# XStepper.net
KiCad netlist of a schematic drawn in EAGLE
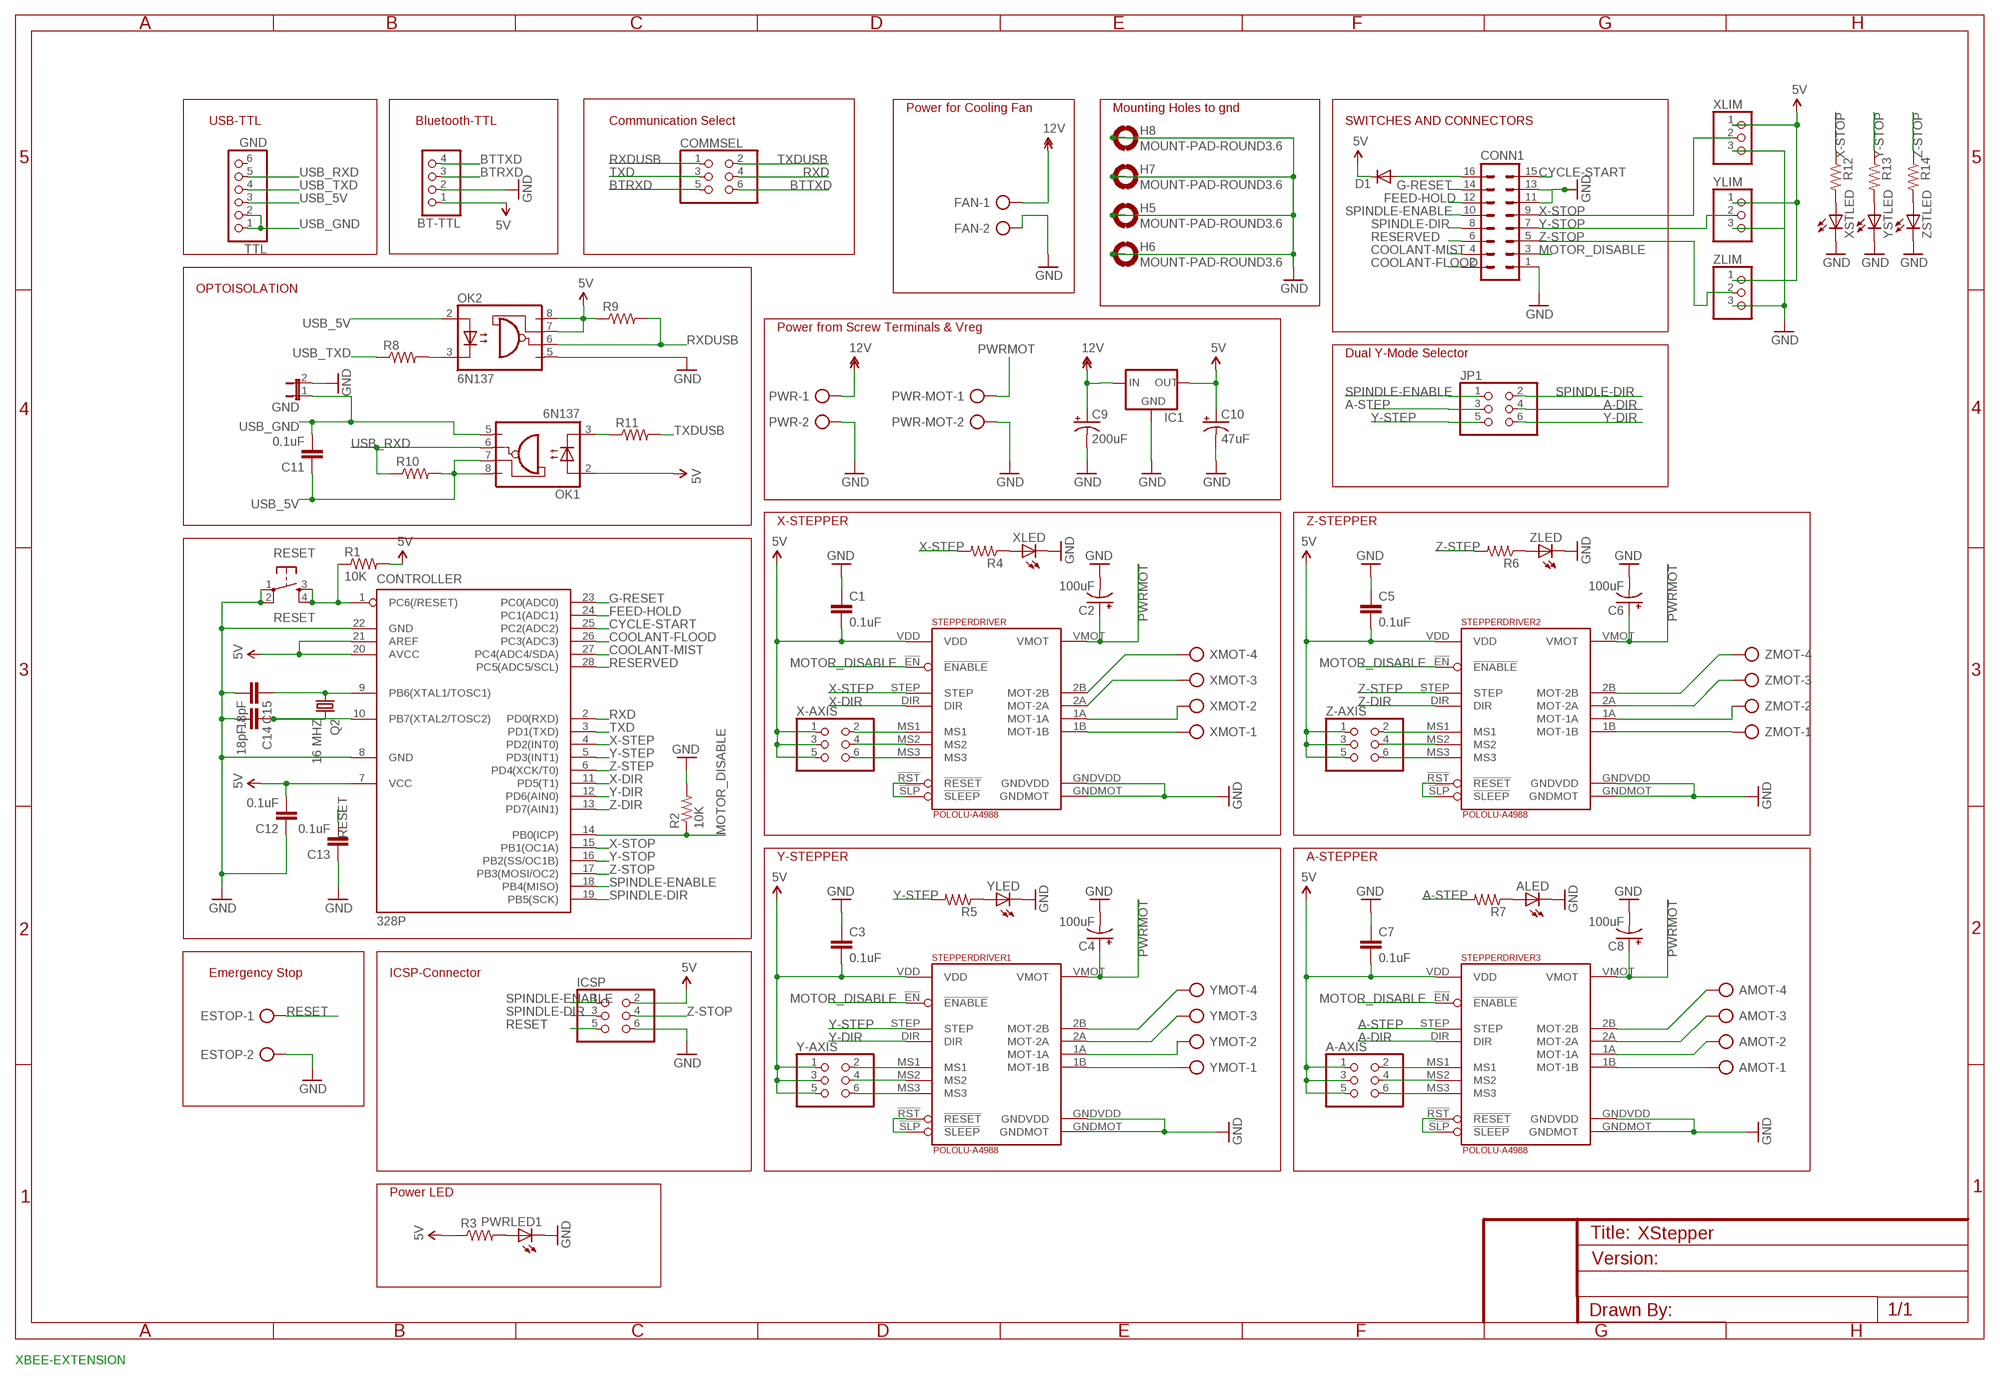
[diagram p0: schematic, sheet 1]

(export (version "E")
  (design (tool "Eeschema 10.0.6"))
  (components
    (comp (ref "328P")
      (value "CONTROLLER")
      (footprint "eagle-import:DIL28-3")
      (libsource (lib "eagle-import") (part "MEGA8-P"))
    )
    (comp (ref "A-AXIS")
      (value "PINHD-2X3")
      (footprint "eagle-import:2X03")
      (libsource (lib "eagle-import") (part "PINHD-2X3"))
    )
    (comp (ref "ALED")
      (value "LED3MM")
      (footprint "eagle-import:LED3MM")
      (libsource (lib "eagle-import") (part "LED3MM"))
    )
    (comp (ref "AMOT")
      (value "AK500/4")
      (footprint "eagle-import:AK500_4")
      (libsource (lib "eagle-import") (part "AK500/4"))
    )
    (comp (ref "BT-TTL")
      (value "PINHD-1X4")
      (footprint "eagle-import:1X04")
      (libsource (lib "eagle-import") (part "PINHD-1X4"))
    )
    (comp (ref "C1")
      (value "0.1uF")
      (footprint "eagle-import:C025-025X050")
      (libsource (lib "eagle-import") (part "C-EU025-025X050"))
    )
    (comp (ref "C2")
      (value "100uF")
      (footprint "eagle-import:E2,5-6")
      (libsource (lib "eagle-import") (part "CPOL-USE2.5-6"))
    )
    (comp (ref "C3")
      (value "0.1uF")
      (footprint "eagle-import:C025-025X050")
      (libsource (lib "eagle-import") (part "C-EU025-025X050"))
    )
    (comp (ref "C4")
      (value "100uF")
      (footprint "eagle-import:E2,5-6")
      (libsource (lib "eagle-import") (part "CPOL-USE2.5-6"))
    )
    (comp (ref "C5")
      (value "0.1uF")
      (footprint "eagle-import:C025-025X050")
      (libsource (lib "eagle-import") (part "C-EU025-025X050"))
    )
    (comp (ref "C6")
      (value "100uF")
      (footprint "eagle-import:E2,5-6")
      (libsource (lib "eagle-import") (part "CPOL-USE2.5-6"))
    )
    (comp (ref "C7")
      (value "0.1uF")
      (footprint "eagle-import:C025-025X050")
      (libsource (lib "eagle-import") (part "C-EU025-025X050"))
    )
    (comp (ref "C8")
      (value "100uF")
      (footprint "eagle-import:E2,5-6")
      (libsource (lib "eagle-import") (part "CPOL-USE2.5-6"))
    )
    (comp (ref "C9")
      (value "200uF")
      (footprint "eagle-import:E2,5-6")
      (libsource (lib "eagle-import") (part "CPOL-USE2.5-6"))
    )
    (comp (ref "C10")
      (value "47uF")
      (footprint "eagle-import:E2,5-6")
      (libsource (lib "eagle-import") (part "CPOL-USE2.5-6"))
    )
    (comp (ref "C11")
      (value "0.1uF")
      (footprint "eagle-import:C025-025X050")
      (libsource (lib "eagle-import") (part "C-EU025-025X050"))
    )
    (comp (ref "C12")
      (value "0.1uF")
      (footprint "eagle-import:C025-025X050")
      (libsource (lib "eagle-import") (part "C-EU025-025X050"))
    )
    (comp (ref "C13")
      (value "0.1uF")
      (footprint "eagle-import:C025-025X050")
      (libsource (lib "eagle-import") (part "C-EU025-025X050"))
    )
    (comp (ref "C14")
      (value "18pF")
      (footprint "eagle-import:C025-025X050")
      (libsource (lib "eagle-import") (part "C-EU025-025X050"))
    )
    (comp (ref "C15")
      (value "18pF")
      (footprint "eagle-import:C025-025X050")
      (libsource (lib "eagle-import") (part "C-EU025-025X050"))
    )
    (comp (ref "COMMSEL")
      (value "PINHD-2X3")
      (footprint "eagle-import:2X03")
      (libsource (lib "eagle-import") (part "PINHD-2X3"))
    )
    (comp (ref "CONN1")
      (value "ML16")
      (footprint "eagle-import:ML16")
      (libsource (lib "eagle-import") (part "ML16"))
    )
    (comp (ref "D1")
      (value "DIODEPTH")
      (footprint "eagle-import:DIODE-1N4001")
      (libsource (lib "eagle-import") (part "DIODEPTH"))
    )
    (comp (ref "ESTOP")
      (value "AK500/2")
      (footprint "eagle-import:AK500_2")
      (libsource (lib "eagle-import") (part "AK500/2"))
    )
    (comp (ref "FAN")
      (value "AK500/2")
      (footprint "eagle-import:AK500_2")
      (libsource (lib "eagle-import") (part "AK500/2"))
    )
    (comp (ref "GND")
      (value "JP1E")
      (footprint "eagle-import:JP1")
      (libsource (lib "eagle-import") (part "JP1E"))
    )
    (comp (ref "H5")
      (value "MOUNT-PAD-ROUND3.6")
      (footprint "eagle-import:3,6-PAD")
      (libsource (lib "eagle-import") (part "MOUNT-PAD-ROUND3.6"))
    )
    (comp (ref "H6")
      (value "MOUNT-PAD-ROUND3.6")
      (footprint "eagle-import:3,6-PAD")
      (libsource (lib "eagle-import") (part "MOUNT-PAD-ROUND3.6"))
    )
    (comp (ref "H7")
      (value "MOUNT-PAD-ROUND3.6")
      (footprint "eagle-import:3,6-PAD")
      (libsource (lib "eagle-import") (part "MOUNT-PAD-ROUND3.6"))
    )
    (comp (ref "H8")
      (value "MOUNT-PAD-ROUND3.6")
      (footprint "eagle-import:3,6-PAD")
      (libsource (lib "eagle-import") (part "MOUNT-PAD-ROUND3.6"))
    )
    (comp (ref "IC1")
      (value "V_REG_78XXSINK")
      (footprint "eagle-import:TO220-IGO")
      (libsource (lib "eagle-import") (part "V_REG_78XXSINK"))
    )
    (comp (ref "ICSP")
      (value "PINHD-2X3")
      (footprint "eagle-import:2X03")
      (libsource (lib "eagle-import") (part "PINHD-2X3"))
    )
    (comp (ref "JP1")
      (value "PINHD-2X3")
      (footprint "eagle-import:2X03")
      (libsource (lib "eagle-import") (part "PINHD-2X3"))
    )
    (comp (ref "OK1")
      (value "6N137")
      (footprint "eagle-import:DIL08")
      (libsource (lib "eagle-import") (part "6N137"))
    )
    (comp (ref "OK2")
      (value "6N137")
      (footprint "eagle-import:DIL08")
      (libsource (lib "eagle-import") (part "6N137"))
    )
    (comp (ref "PWR")
      (value "AK500/2")
      (footprint "eagle-import:AK500_2")
      (libsource (lib "eagle-import") (part "AK500/2"))
    )
    (comp (ref "PWR-MOT")
      (value "AK500/2")
      (footprint "eagle-import:AK500_2")
      (libsource (lib "eagle-import") (part "AK500/2"))
    )
    (comp (ref "PWRLED1")
      (value "LED3MM")
      (footprint "eagle-import:LED3MM")
      (libsource (lib "eagle-import") (part "LED3MM"))
    )
    (comp (ref "Q2")
      (value "16 MHZ")
      (footprint "eagle-import:HC49_S")
      (libsource (lib "eagle-import") (part "CRYSTALHC49S"))
    )
    (comp (ref "R1")
      (value "10K")
      (footprint "eagle-import:AXIAL-0.3")
      (libsource (lib "eagle-import") (part "RESISTORAXIAL-0.3"))
    )
    (comp (ref "R2")
      (value "10K")
      (footprint "eagle-import:AXIAL-0.3")
      (libsource (lib "eagle-import") (part "RESISTORAXIAL-0.3"))
    )
    (comp (ref "R3")
      (value "RESISTORAXIAL-0.3")
      (footprint "eagle-import:AXIAL-0.3")
      (libsource (lib "eagle-import") (part "RESISTORAXIAL-0.3"))
    )
    (comp (ref "R4")
      (value "RESISTORAXIAL-0.3")
      (footprint "eagle-import:AXIAL-0.3")
      (libsource (lib "eagle-import") (part "RESISTORAXIAL-0.3"))
    )
    (comp (ref "R5")
      (value "RESISTORAXIAL-0.3")
      (footprint "eagle-import:AXIAL-0.3")
      (libsource (lib "eagle-import") (part "RESISTORAXIAL-0.3"))
    )
    (comp (ref "R6")
      (value "RESISTORAXIAL-0.3")
      (footprint "eagle-import:AXIAL-0.3")
      (libsource (lib "eagle-import") (part "RESISTORAXIAL-0.3"))
    )
    (comp (ref "R7")
      (value "RESISTORAXIAL-0.3")
      (footprint "eagle-import:AXIAL-0.3")
      (libsource (lib "eagle-import") (part "RESISTORAXIAL-0.3"))
    )
    (comp (ref "R8")
      (value "RESISTORAXIAL-0.3")
      (footprint "eagle-import:AXIAL-0.3")
      (libsource (lib "eagle-import") (part "RESISTORAXIAL-0.3"))
    )
    (comp (ref "R9")
      (value "RESISTORAXIAL-0.3")
      (footprint "eagle-import:AXIAL-0.3")
      (libsource (lib "eagle-import") (part "RESISTORAXIAL-0.3"))
    )
    (comp (ref "R10")
      (value "RESISTORAXIAL-0.3")
      (footprint "eagle-import:AXIAL-0.3")
      (libsource (lib "eagle-import") (part "RESISTORAXIAL-0.3"))
    )
    (comp (ref "R11")
      (value "RESISTORAXIAL-0.3")
      (footprint "eagle-import:AXIAL-0.3")
      (libsource (lib "eagle-import") (part "RESISTORAXIAL-0.3"))
    )
    (comp (ref "R12")
      (value "RESISTORAXIAL-0.3")
      (footprint "eagle-import:AXIAL-0.3")
      (libsource (lib "eagle-import") (part "RESISTORAXIAL-0.3"))
    )
    (comp (ref "R13")
      (value "RESISTORAXIAL-0.3")
      (footprint "eagle-import:AXIAL-0.3")
      (libsource (lib "eagle-import") (part "RESISTORAXIAL-0.3"))
    )
    (comp (ref "R14")
      (value "RESISTORAXIAL-0.3")
      (footprint "eagle-import:AXIAL-0.3")
      (libsource (lib "eagle-import") (part "RESISTORAXIAL-0.3"))
    )
    (comp (ref "RESET")
      (value "RESET")
      (footprint "eagle-import:TACTILE-PTH")
      (libsource (lib "eagle-import") (part "TAC_SWITCHPTH"))
    )
    (comp (ref "STEPPERDRIVER")
      (value "POLOLU-A4988")
      (footprint "eagle-import:POLOLU-ALLEGRO-PTH")
      (libsource (lib "eagle-import") (part "POLOLU-ALLEGRO"))
    )
    (comp (ref "STEPPERDRIVER1")
      (value "POLOLU-A4988")
      (footprint "eagle-import:POLOLU-ALLEGRO-PTH")
      (libsource (lib "eagle-import") (part "POLOLU-ALLEGRO"))
    )
    (comp (ref "STEPPERDRIVER2")
      (value "POLOLU-A4988")
      (footprint "eagle-import:POLOLU-ALLEGRO-PTH")
      (libsource (lib "eagle-import") (part "POLOLU-ALLEGRO"))
    )
    (comp (ref "STEPPERDRIVER3")
      (value "POLOLU-A4988")
      (footprint "eagle-import:POLOLU-ALLEGRO-PTH")
      (libsource (lib "eagle-import") (part "POLOLU-ALLEGRO"))
    )
    (comp (ref "TTL")
      (value "GND")
      (footprint "eagle-import:1X06")
      (libsource (lib "eagle-import") (part "PINHD-1X6"))
    )
    (comp (ref "X-AXIS")
      (value "PINHD-2X3")
      (footprint "eagle-import:2X03")
      (libsource (lib "eagle-import") (part "PINHD-2X3"))
    )
    (comp (ref "XLED")
      (value "LED3MM")
      (footprint "eagle-import:LED3MM")
      (libsource (lib "eagle-import") (part "LED3MM"))
    )
    (comp (ref "XLIM")
      (value "PINHD-1X3")
      (footprint "eagle-import:1X03")
      (libsource (lib "eagle-import") (part "PINHD-1X3"))
    )
    (comp (ref "XMOT")
      (value "AK500/4")
      (footprint "eagle-import:AK500_4")
      (libsource (lib "eagle-import") (part "AK500/4"))
    )
    (comp (ref "XSTLED")
      (value "LED3MM")
      (footprint "eagle-import:LED3MM")
      (libsource (lib "eagle-import") (part "LED3MM"))
    )
    (comp (ref "Y-AXIS")
      (value "PINHD-2X3")
      (footprint "eagle-import:2X03")
      (libsource (lib "eagle-import") (part "PINHD-2X3"))
    )
    (comp (ref "YLED")
      (value "LED3MM")
      (footprint "eagle-import:LED3MM")
      (libsource (lib "eagle-import") (part "LED3MM"))
    )
    (comp (ref "YLIM")
      (value "PINHD-1X3")
      (footprint "eagle-import:1X03")
      (libsource (lib "eagle-import") (part "PINHD-1X3"))
    )
    (comp (ref "YMOT")
      (value "AK500/4")
      (footprint "eagle-import:AK500_4")
      (libsource (lib "eagle-import") (part "AK500/4"))
    )
    (comp (ref "YSTLED")
      (value "LED3MM")
      (footprint "eagle-import:LED3MM")
      (libsource (lib "eagle-import") (part "LED3MM"))
    )
    (comp (ref "Z-AXIS")
      (value "PINHD-2X3")
      (footprint "eagle-import:2X03")
      (libsource (lib "eagle-import") (part "PINHD-2X3"))
    )
    (comp (ref "ZLED")
      (value "LED3MM")
      (footprint "eagle-import:LED3MM")
      (libsource (lib "eagle-import") (part "LED3MM"))
    )
    (comp (ref "ZLIM")
      (value "PINHD-1X3")
      (footprint "eagle-import:1X03")
      (libsource (lib "eagle-import") (part "PINHD-1X3"))
    )
    (comp (ref "ZMOT")
      (value "AK500/4")
      (footprint "eagle-import:AK500_4")
      (libsource (lib "eagle-import") (part "AK500/4"))
    )
    (comp (ref "ZSTLED")
      (value "LED3MM")
      (footprint "eagle-import:LED3MM")
      (libsource (lib "eagle-import") (part "LED3MM"))
    )
  )
  (nets
    (net (code "1") (name "/A-DIR") (class "Default")
      (node (ref "JP1") (pin "4") (pinfunction "4_4") (pintype "passive"))
      (node (ref "STEPPERDRIVER3") (pin "DIR") (pinfunction "DIR_DIR") (pintype "bidirectional"))
    )
    (net (code "2") (name "/A-STEP") (class "Default")
      (node (ref "JP1") (pin "3") (pinfunction "3_3") (pintype "passive"))
      (node (ref "R7") (pin "P$2") (pinfunction "2_P$2") (pintype "passive"))
      (node (ref "STEPPERDRIVER3") (pin "STEP") (pinfunction "STEP_STEP") (pintype "bidirectional"))
    )
    (net (code "3") (name "/BTRXD") (class "Default")
      (node (ref "BT-TTL") (pin "3") (pinfunction "3_3") (pintype "passive"))
      (node (ref "COMMSEL") (pin "5") (pinfunction "5_5") (pintype "passive"))
    )
    (net (code "4") (name "/BTTXD") (class "Default")
      (node (ref "BT-TTL") (pin "4") (pinfunction "4_4") (pintype "passive"))
      (node (ref "COMMSEL") (pin "6") (pinfunction "6_6") (pintype "passive"))
    )
    (net (code "5") (name "/COOLANT-FLOOD") (class "Default")
      (node (ref "328P") (pin "26") (pinfunction "PC3(ADC3)_26") (pintype "bidirectional"))
      (node (ref "CONN1") (pin "2") (pinfunction "2_2") (pintype "passive"))
    )
    (net (code "6") (name "/COOLANT-MIST") (class "Default")
      (node (ref "328P") (pin "27") (pinfunction "PC4(ADC4/SDA)_27") (pintype "bidirectional"))
      (node (ref "CONN1") (pin "4") (pinfunction "4_4") (pintype "passive"))
    )
    (net (code "7") (name "/CYCLE-START") (class "Default")
      (node (ref "328P") (pin "25") (pinfunction "PC2(ADC2)_25") (pintype "bidirectional"))
      (node (ref "CONN1") (pin "15") (pinfunction "15_15") (pintype "passive"))
    )
    (net (code "8") (name "/FEED-HOLD") (class "Default")
      (node (ref "328P") (pin "24") (pinfunction "PC1(ADC1)_24") (pintype "bidirectional"))
      (node (ref "CONN1") (pin "12") (pinfunction "12_12") (pintype "passive"))
    )
    (net (code "9") (name "/G-RESET") (class "Default")
      (node (ref "328P") (pin "23") (pinfunction "PC0(ADC0)_23") (pintype "bidirectional"))
      (node (ref "CONN1") (pin "14") (pinfunction "14_14") (pintype "passive"))
    )
    (net (code "10") (name "/MOTOR_DISABLE") (class "Default")
      (node (ref "328P") (pin "14") (pinfunction "PB0(ICP)_14") (pintype "bidirectional"))
      (node (ref "CONN1") (pin "3") (pinfunction "3_3") (pintype "passive"))
      (node (ref "R2") (pin "P$1") (pinfunction "1_P$1") (pintype "passive"))
      (node (ref "STEPPERDRIVER") (pin "!EN") (pinfunction "~{ENABLE}_!EN") (pintype "input"))
      (node (ref "STEPPERDRIVER1") (pin "!EN") (pinfunction "~{ENABLE}_!EN") (pintype "input"))
      (node (ref "STEPPERDRIVER2") (pin "!EN") (pinfunction "~{ENABLE}_!EN") (pintype "input"))
      (node (ref "STEPPERDRIVER3") (pin "!EN") (pinfunction "~{ENABLE}_!EN") (pintype "input"))
    )
    (net (code "11") (name "/PWRMOT") (class "Default")
      (node (ref "C2") (pin "+") (pinfunction "+_+") (pintype "passive"))
      (node (ref "C4") (pin "+") (pinfunction "+_+") (pintype "passive"))
      (node (ref "C6") (pin "+") (pinfunction "+_+") (pintype "passive"))
      (node (ref "C8") (pin "+") (pinfunction "+_+") (pintype "passive"))
      (node (ref "PWR-MOT") (pin "1") (pinfunction "KL_1") (pintype "passive"))
      (node (ref "STEPPERDRIVER") (pin "VMOT") (pinfunction "VMOT_VMOT") (pintype "power_in"))
      (node (ref "STEPPERDRIVER1") (pin "VMOT") (pinfunction "VMOT_VMOT") (pintype "power_in"))
      (node (ref "STEPPERDRIVER2") (pin "VMOT") (pinfunction "VMOT_VMOT") (pintype "power_in"))
      (node (ref "STEPPERDRIVER3") (pin "VMOT") (pinfunction "VMOT_VMOT") (pintype "power_in"))
    )
    (net (code "12") (name "/RESERVED") (class "Default")
      (node (ref "328P") (pin "28") (pinfunction "PC5(ADC5/SCL)_28") (pintype "bidirectional"))
      (node (ref "CONN1") (pin "6") (pinfunction "6_6") (pintype "passive"))
    )
    (net (code "13") (name "/RESET") (class "Default")
      (node (ref "328P") (pin "1") (pinfunction "PC6(/RESET)_1") (pintype "bidirectional"))
      (node (ref "C13") (pin "2") (pinfunction "2_2") (pintype "passive"))
      (node (ref "ESTOP") (pin "1") (pinfunction "KL_1") (pintype "passive"))
      (node (ref "ICSP") (pin "5") (pinfunction "5_5") (pintype "passive"))
      (node (ref "R1") (pin "P$1") (pinfunction "1_P$1") (pintype "passive"))
      (node (ref "RESET") (pin "3") (pinfunction "3_3") (pintype "passive"))
      (node (ref "RESET") (pin "4") (pinfunction "4_4") (pintype "passive"))
    )
    (net (code "14") (name "/RXD") (class "Default")
      (node (ref "328P") (pin "2") (pinfunction "PD0(RXD)_2") (pintype "bidirectional"))
      (node (ref "COMMSEL") (pin "4") (pinfunction "4_4") (pintype "passive"))
    )
    (net (code "15") (name "/RXDUSB") (class "Default")
      (node (ref "COMMSEL") (pin "1") (pinfunction "1_1") (pintype "passive"))
      (node (ref "OK2") (pin "6") (pinfunction "VO_6") (pintype "passive"))
      (node (ref "R9") (pin "P$2") (pinfunction "2_P$2") (pintype "passive"))
    )
    (net (code "16") (name "/SPINDLE-DIR") (class "Default")
      (node (ref "328P") (pin "19") (pinfunction "PB5(SCK)_19") (pintype "bidirectional"))
      (node (ref "CONN1") (pin "8") (pinfunction "8_8") (pintype "passive"))
      (node (ref "ICSP") (pin "3") (pinfunction "3_3") (pintype "passive"))
      (node (ref "JP1") (pin "2") (pinfunction "2_2") (pintype "passive"))
    )
    (net (code "17") (name "/SPINDLE-ENABLE") (class "Default")
      (node (ref "328P") (pin "18") (pinfunction "PB4(MISO)_18") (pintype "bidirectional"))
      (node (ref "CONN1") (pin "10") (pinfunction "10_10") (pintype "passive"))
      (node (ref "ICSP") (pin "1") (pinfunction "1_1") (pintype "passive"))
      (node (ref "JP1") (pin "1") (pinfunction "1_1") (pintype "passive"))
    )
    (net (code "18") (name "/TXD") (class "Default")
      (node (ref "328P") (pin "3") (pinfunction "PD1(TXD)_3") (pintype "bidirectional"))
      (node (ref "COMMSEL") (pin "3") (pinfunction "3_3") (pintype "passive"))
    )
    (net (code "19") (name "/TXDUSB") (class "Default")
      (node (ref "COMMSEL") (pin "2") (pinfunction "2_2") (pintype "passive"))
      (node (ref "R11") (pin "P$2") (pinfunction "2_P$2") (pintype "passive"))
    )
    (net (code "20") (name "/USB_5V") (class "Default")
      (node (ref "C11") (pin "1") (pinfunction "1_1") (pintype "passive"))
      (node (ref "OK1") (pin "7") (pinfunction "VE_7") (pintype "passive"))
      (node (ref "OK1") (pin "8") (pinfunction "VCC_8") (pintype "passive"))
      (node (ref "OK2") (pin "2") (pinfunction "A_2") (pintype "passive"))
      (node (ref "R10") (pin "P$2") (pinfunction "2_P$2") (pintype "passive"))
      (node (ref "TTL") (pin "3") (pinfunction "3_3") (pintype "passive"))
    )
    (net (code "21") (name "/USB_GND") (class "Default")
      (node (ref "C11") (pin "2") (pinfunction "2_2") (pintype "passive"))
      (node (ref "GND") (pin "1") (pinfunction "1_1") (pintype "passive"))
      (node (ref "OK1") (pin "5") (pinfunction "GND_5") (pintype "passive"))
      (node (ref "TTL") (pin "1") (pinfunction "1_1") (pintype "passive"))
      (node (ref "TTL") (pin "2") (pinfunction "2_2") (pintype "passive"))
    )
    (net (code "22") (name "/USB_RXD") (class "Default")
      (node (ref "OK1") (pin "6") (pinfunction "VO_6") (pintype "passive"))
      (node (ref "R10") (pin "P$1") (pinfunction "1_P$1") (pintype "passive"))
      (node (ref "TTL") (pin "5") (pinfunction "5_5") (pintype "passive"))
    )
    (net (code "23") (name "/USB_TXD") (class "Default")
      (node (ref "R8") (pin "P$1") (pinfunction "1_P$1") (pintype "passive"))
      (node (ref "TTL") (pin "4") (pinfunction "4_4") (pintype "passive"))
    )
    (net (code "24") (name "/X-DIR") (class "Default")
      (node (ref "328P") (pin "11") (pinfunction "PD5(T1)_11") (pintype "bidirectional"))
      (node (ref "STEPPERDRIVER") (pin "DIR") (pinfunction "DIR_DIR") (pintype "bidirectional"))
    )
    (net (code "25") (name "/X-STEP") (class "Default")
      (node (ref "328P") (pin "4") (pinfunction "PD2(INT0)_4") (pintype "bidirectional"))
      (node (ref "R4") (pin "P$2") (pinfunction "2_P$2") (pintype "passive"))
      (node (ref "STEPPERDRIVER") (pin "STEP") (pinfunction "STEP_STEP") (pintype "bidirectional"))
    )
    (net (code "26") (name "/X-STOP") (class "Default")
      (node (ref "328P") (pin "15") (pinfunction "PB1(OC1A)_15") (pintype "bidirectional"))
      (node (ref "CONN1") (pin "9") (pinfunction "9_9") (pintype "passive"))
      (node (ref "R12") (pin "P$1") (pinfunction "1_P$1") (pintype "passive"))
      (node (ref "XLIM") (pin "2") (pinfunction "2_2") (pintype "passive"))
    )
    (net (code "27") (name "/Y-DIR") (class "Default")
      (node (ref "328P") (pin "12") (pinfunction "PD6(AIN0)_12") (pintype "bidirectional"))
      (node (ref "JP1") (pin "6") (pinfunction "6_6") (pintype "passive"))
      (node (ref "STEPPERDRIVER1") (pin "DIR") (pinfunction "DIR_DIR") (pintype "bidirectional"))
    )
    (net (code "28") (name "/Y-STEP") (class "Default")
      (node (ref "328P") (pin "5") (pinfunction "PD3(INT1)_5") (pintype "bidirectional"))
      (node (ref "JP1") (pin "5") (pinfunction "5_5") (pintype "passive"))
      (node (ref "R5") (pin "P$2") (pinfunction "2_P$2") (pintype "passive"))
      (node (ref "STEPPERDRIVER1") (pin "STEP") (pinfunction "STEP_STEP") (pintype "bidirectional"))
    )
    (net (code "29") (name "/Y-STOP") (class "Default")
      (node (ref "328P") (pin "16") (pinfunction "PB2(SS/OC1B)_16") (pintype "bidirectional"))
      (node (ref "CONN1") (pin "7") (pinfunction "7_7") (pintype "passive"))
      (node (ref "R13") (pin "P$1") (pinfunction "1_P$1") (pintype "passive"))
      (node (ref "YLIM") (pin "2") (pinfunction "2_2") (pintype "passive"))
    )
    (net (code "30") (name "/Z-DIR") (class "Default")
      (node (ref "328P") (pin "13") (pinfunction "PD7(AIN1)_13") (pintype "bidirectional"))
      (node (ref "STEPPERDRIVER2") (pin "DIR") (pinfunction "DIR_DIR") (pintype "bidirectional"))
    )
    (net (code "31") (name "/Z-STEP") (class "Default")
      (node (ref "328P") (pin "6") (pinfunction "PD4(XCK/T0)_6") (pintype "bidirectional"))
      (node (ref "R6") (pin "P$2") (pinfunction "2_P$2") (pintype "passive"))
      (node (ref "STEPPERDRIVER2") (pin "STEP") (pinfunction "STEP_STEP") (pintype "bidirectional"))
    )
    (net (code "32") (name "/Z-STOP") (class "Default")
      (node (ref "328P") (pin "17") (pinfunction "PB3(MOSI/OC2)_17") (pintype "bidirectional"))
      (node (ref "CONN1") (pin "5") (pinfunction "5_5") (pintype "passive"))
      (node (ref "ICSP") (pin "4") (pinfunction "4_4") (pintype "passive"))
      (node (ref "R14") (pin "P$1") (pinfunction "1_P$1") (pintype "passive"))
      (node (ref "ZLIM") (pin "2") (pinfunction "2_2") (pintype "passive"))
    )
    (net (code "33") (name "5V") (class "Default")
      (node (ref "328P") (pin "20") (pinfunction "AVCC_20") (pintype "power_in"))
      (node (ref "328P") (pin "21") (pinfunction "AREF_21") (pintype "passive"))
      (node (ref "328P") (pin "7") (pinfunction "VCC_7") (pintype "power_in"))
      (node (ref "A-AXIS") (pin "1") (pinfunction "1_1") (pintype "passive"))
      (node (ref "A-AXIS") (pin "3") (pinfunction "3_3") (pintype "passive"))
      (node (ref "A-AXIS") (pin "5") (pinfunction "5_5") (pintype "passive"))
      (node (ref "BT-TTL") (pin "1") (pinfunction "1_1") (pintype "passive"))
      (node (ref "C1") (pin "2") (pinfunction "2_2") (pintype "passive"))
      (node (ref "C10") (pin "+") (pinfunction "+_+") (pintype "passive"))
      (node (ref "C12") (pin "2") (pinfunction "2_2") (pintype "passive"))
      (node (ref "C3") (pin "2") (pinfunction "2_2") (pintype "passive"))
      (node (ref "C5") (pin "2") (pinfunction "2_2") (pintype "passive"))
      (node (ref "C7") (pin "2") (pinfunction "2_2") (pintype "passive"))
      (node (ref "D1") (pin "C") (pinfunction "C_C") (pintype "passive"))
      (node (ref "IC1") (pin "OUT") (pinfunction "OUT_OUT") (pintype "output"))
      (node (ref "ICSP") (pin "2") (pinfunction "2_2") (pintype "passive"))
      (node (ref "OK1") (pin "2") (pinfunction "A_2") (pintype "passive"))
      (node (ref "OK2") (pin "7") (pinfunction "VE_7") (pintype "passive"))
      (node (ref "OK2") (pin "8") (pinfunction "VCC_8") (pintype "passive"))
      (node (ref "R1") (pin "P$2") (pinfunction "2_P$2") (pintype "passive"))
      (node (ref "R3") (pin "P$1") (pinfunction "1_P$1") (pintype "passive"))
      (node (ref "R9") (pin "P$1") (pinfunction "1_P$1") (pintype "passive"))
      (node (ref "STEPPERDRIVER") (pin "VDD") (pinfunction "VDD_VDD") (pintype "power_in"))
      (node (ref "STEPPERDRIVER1") (pin "VDD") (pinfunction "VDD_VDD") (pintype "power_in"))
      (node (ref "STEPPERDRIVER2") (pin "VDD") (pinfunction "VDD_VDD") (pintype "power_in"))
      (node (ref "STEPPERDRIVER3") (pin "VDD") (pinfunction "VDD_VDD") (pintype "power_in"))
      (node (ref "X-AXIS") (pin "1") (pinfunction "1_1") (pintype "passive"))
      (node (ref "X-AXIS") (pin "3") (pinfunction "3_3") (pintype "passive"))
      (node (ref "X-AXIS") (pin "5") (pinfunction "5_5") (pintype "passive"))
      (node (ref "XLIM") (pin "1") (pinfunction "1_1") (pintype "passive"))
      (node (ref "Y-AXIS") (pin "1") (pinfunction "1_1") (pintype "passive"))
      (node (ref "Y-AXIS") (pin "3") (pinfunction "3_3") (pintype "passive"))
      (node (ref "Y-AXIS") (pin "5") (pinfunction "5_5") (pintype "passive"))
      (node (ref "YLIM") (pin "1") (pinfunction "1_1") (pintype "passive"))
      (node (ref "Z-AXIS") (pin "1") (pinfunction "1_1") (pintype "passive"))
      (node (ref "Z-AXIS") (pin "3") (pinfunction "3_3") (pintype "passive"))
      (node (ref "Z-AXIS") (pin "5") (pinfunction "5_5") (pintype "passive"))
      (node (ref "ZLIM") (pin "1") (pinfunction "1_1") (pintype "passive"))
    )
    (net (code "34") (name "12V") (class "Default")
      (node (ref "C9") (pin "+") (pinfunction "+_+") (pintype "passive"))
      (node (ref "FAN") (pin "1") (pinfunction "KL_1") (pintype "passive"))
      (node (ref "IC1") (pin "IN") (pinfunction "IN_IN") (pintype "input"))
      (node (ref "PWR") (pin "1") (pinfunction "KL_1") (pintype "passive"))
    )
    (net (code "35") (name "GND") (class "Default")
      (node (ref "328P") (pin "22") (pinfunction "GND_22") (pintype "power_in"))
      (node (ref "328P") (pin "8") (pinfunction "GND_8") (pintype "power_in"))
      (node (ref "ALED") (pin "K") (pinfunction "C_K") (pintype "passive"))
      (node (ref "BT-TTL") (pin "2") (pinfunction "2_2") (pintype "passive"))
      (node (ref "C1") (pin "1") (pinfunction "1_1") (pintype "passive"))
      (node (ref "C10") (pin "-") (pinfunction "-_-") (pintype "passive"))
      (node (ref "C12") (pin "1") (pinfunction "1_1") (pintype "passive"))
      (node (ref "C13") (pin "1") (pinfunction "1_1") (pintype "passive"))
      (node (ref "C14") (pin "2") (pinfunction "2_2") (pintype "passive"))
      (node (ref "C15") (pin "2") (pinfunction "2_2") (pintype "passive"))
      (node (ref "C2") (pin "-") (pinfunction "-_-") (pintype "passive"))
      (node (ref "C3") (pin "1") (pinfunction "1_1") (pintype "passive"))
      (node (ref "C4") (pin "-") (pinfunction "-_-") (pintype "passive"))
      (node (ref "C5") (pin "1") (pinfunction "1_1") (pintype "passive"))
      (node (ref "C6") (pin "-") (pinfunction "-_-") (pintype "passive"))
      (node (ref "C7") (pin "1") (pinfunction "1_1") (pintype "passive"))
      (node (ref "C8") (pin "-") (pinfunction "-_-") (pintype "passive"))
      (node (ref "C9") (pin "-") (pinfunction "-_-") (pintype "passive"))
      (node (ref "CONN1") (pin "1") (pinfunction "1_1") (pintype "passive"))
      (node (ref "CONN1") (pin "11") (pinfunction "11_11") (pintype "passive"))
      (node (ref "CONN1") (pin "13") (pinfunction "13_13") (pintype "passive"))
      (node (ref "ESTOP") (pin "2") (pinfunction "KL_2") (pintype "passive"))
      (node (ref "FAN") (pin "2") (pinfunction "KL_2") (pintype "passive"))
      (node (ref "GND") (pin "2") (pinfunction "2_2") (pintype "passive"))
      (node (ref "H5") (pin "B3,6") (pinfunction "MOUNT_B3,6") (pintype "passive"))
      (node (ref "H6") (pin "B3,6") (pinfunction "MOUNT_B3,6") (pintype "passive"))
      (node (ref "H7") (pin "B3,6") (pinfunction "MOUNT_B3,6") (pintype "passive"))
      (node (ref "H8") (pin "B3,6") (pinfunction "MOUNT_B3,6") (pintype "passive"))
      (node (ref "IC1") (pin "GND") (pinfunction "GND_GND") (pintype "input"))
      (node (ref "ICSP") (pin "6") (pinfunction "6_6") (pintype "passive"))
      (node (ref "OK2") (pin "5") (pinfunction "GND_5") (pintype "passive"))
      (node (ref "PWR") (pin "2") (pinfunction "KL_2") (pintype "passive"))
      (node (ref "PWR-MOT") (pin "2") (pinfunction "KL_2") (pintype "passive"))
      (node (ref "PWRLED1") (pin "K") (pinfunction "C_K") (pintype "passive"))
      (node (ref "R2") (pin "P$2") (pinfunction "2_P$2") (pintype "passive"))
      (node (ref "RESET") (pin "1") (pinfunction "1_1") (pintype "passive"))
      (node (ref "RESET") (pin "2") (pinfunction "2_2") (pintype "passive"))
      (node (ref "STEPPERDRIVER") (pin "GNDMOT") (pinfunction "GNDMOT_GNDMOT") (pintype "power_in"))
      (node (ref "STEPPERDRIVER") (pin "GNDVDD") (pinfunction "GNDVDD_GNDVDD") (pintype "power_in"))
      (node (ref "STEPPERDRIVER1") (pin "GNDMOT") (pinfunction "GNDMOT_GNDMOT") (pintype "power_in"))
      (node (ref "STEPPERDRIVER1") (pin "GNDVDD") (pinfunction "GNDVDD_GNDVDD") (pintype "power_in"))
      (node (ref "STEPPERDRIVER2") (pin "GNDMOT") (pinfunction "GNDMOT_GNDMOT") (pintype "power_in"))
      (node (ref "STEPPERDRIVER2") (pin "GNDVDD") (pinfunction "GNDVDD_GNDVDD") (pintype "power_in"))
      (node (ref "STEPPERDRIVER3") (pin "GNDMOT") (pinfunction "GNDMOT_GNDMOT") (pintype "power_in"))
      (node (ref "STEPPERDRIVER3") (pin "GNDVDD") (pinfunction "GNDVDD_GNDVDD") (pintype "power_in"))
      (node (ref "XLED") (pin "K") (pinfunction "C_K") (pintype "passive"))
      (node (ref "XLIM") (pin "3") (pinfunction "3_3") (pintype "passive"))
      (node (ref "XSTLED") (pin "K") (pinfunction "C_K") (pintype "passive"))
      (node (ref "YLED") (pin "K") (pinfunction "C_K") (pintype "passive"))
      (node (ref "YLIM") (pin "3") (pinfunction "3_3") (pintype "passive"))
      (node (ref "YSTLED") (pin "K") (pinfunction "C_K") (pintype "passive"))
      (node (ref "ZLED") (pin "K") (pinfunction "C_K") (pintype "passive"))
      (node (ref "ZLIM") (pin "3") (pinfunction "3_3") (pintype "passive"))
      (node (ref "ZSTLED") (pin "K") (pinfunction "C_K") (pintype "passive"))
    )
    (net (code "36") (name "Net-(328P-PB6(XTAL1{slash}TOSC1))") (class "Default")
      (node (ref "328P") (pin "9") (pinfunction "PB6(XTAL1/TOSC1)_9") (pintype "bidirectional"))
      (node (ref "C15") (pin "1") (pinfunction "1_1") (pintype "passive"))
      (node (ref "Q2") (pin "1") (pinfunction "1_1") (pintype "passive"))
    )
    (net (code "37") (name "Net-(328P-PB7(XTAL2{slash}TOSC2))") (class "Default")
      (node (ref "328P") (pin "10") (pinfunction "PB7(XTAL2/TOSC2)_10") (pintype "bidirectional"))
      (node (ref "C14") (pin "1") (pinfunction "1_1") (pintype "passive"))
      (node (ref "Q2") (pin "2") (pinfunction "2_2") (pintype "passive"))
    )
    (net (code "38") (name "Net-(A-AXIS-Pad2)") (class "Default")
      (node (ref "A-AXIS") (pin "2") (pinfunction "2_2") (pintype "passive"))
      (node (ref "STEPPERDRIVER3") (pin "MS1") (pinfunction "MS1_MS1") (pintype "input"))
    )
    (net (code "39") (name "Net-(A-AXIS-Pad4)") (class "Default")
      (node (ref "A-AXIS") (pin "4") (pinfunction "4_4") (pintype "passive"))
      (node (ref "STEPPERDRIVER3") (pin "MS2") (pinfunction "MS2_MS2") (pintype "input"))
    )
    (net (code "40") (name "Net-(A-AXIS-Pad6)") (class "Default")
      (node (ref "A-AXIS") (pin "6") (pinfunction "6_6") (pintype "passive"))
      (node (ref "STEPPERDRIVER3") (pin "MS3") (pinfunction "MS3_MS3") (pintype "input"))
    )
    (net (code "41") (name "Net-(AMOTA-KL)") (class "Default")
      (node (ref "AMOT") (pin "1") (pinfunction "KL_1") (pintype "passive"))
      (node (ref "STEPPERDRIVER3") (pin "1B") (pinfunction "MOT-1B_1B") (pintype "power_in"))
    )
    (net (code "42") (name "Net-(AMOTB-KL)") (class "Default")
      (node (ref "AMOT") (pin "2") (pinfunction "KL_2") (pintype "passive"))
      (node (ref "STEPPERDRIVER3") (pin "1A") (pinfunction "MOT-1A_1A") (pintype "power_in"))
    )
    (net (code "43") (name "Net-(AMOTC-KL)") (class "Default")
      (node (ref "AMOT") (pin "3") (pinfunction "KL_3") (pintype "passive"))
      (node (ref "STEPPERDRIVER3") (pin "2A") (pinfunction "MOT-2A_2A") (pintype "power_in"))
    )
    (net (code "44") (name "Net-(AMOTD-KL)") (class "Default")
      (node (ref "AMOT") (pin "4") (pinfunction "KL_4") (pintype "passive"))
      (node (ref "STEPPERDRIVER3") (pin "2B") (pinfunction "MOT-2B_2B") (pintype "power_in"))
    )
    (net (code "45") (name "Net-(CONN1-Pad16)") (class "Default")
      (node (ref "CONN1") (pin "16") (pinfunction "16_16") (pintype "passive"))
      (node (ref "D1") (pin "A") (pinfunction "A_A") (pintype "passive"))
    )
    (net (code "46") (name "Net-(OK1-C)") (class "Default")
      (node (ref "OK1") (pin "3") (pinfunction "C_3") (pintype "passive"))
      (node (ref "R11") (pin "P$1") (pinfunction "1_P$1") (pintype "passive"))
    )
    (net (code "47") (name "Net-(OK2-C)") (class "Default")
      (node (ref "OK2") (pin "3") (pinfunction "C_3") (pintype "passive"))
      (node (ref "R8") (pin "P$2") (pinfunction "2_P$2") (pintype "passive"))
    )
    (net (code "48") (name "Net-(R3-2)") (class "Default")
      (node (ref "PWRLED1") (pin "A") (pinfunction "A_A") (pintype "passive"))
      (node (ref "R3") (pin "P$2") (pinfunction "2_P$2") (pintype "passive"))
    )
    (net (code "49") (name "Net-(R4-1)") (class "Default")
      (node (ref "R4") (pin "P$1") (pinfunction "1_P$1") (pintype "passive"))
      (node (ref "XLED") (pin "A") (pinfunction "A_A") (pintype "passive"))
    )
    (net (code "50") (name "Net-(R5-1)") (class "Default")
      (node (ref "R5") (pin "P$1") (pinfunction "1_P$1") (pintype "passive"))
      (node (ref "YLED") (pin "A") (pinfunction "A_A") (pintype "passive"))
    )
    (net (code "51") (name "Net-(R6-1)") (class "Default")
      (node (ref "R6") (pin "P$1") (pinfunction "1_P$1") (pintype "passive"))
      (node (ref "ZLED") (pin "A") (pinfunction "A_A") (pintype "passive"))
    )
    (net (code "52") (name "Net-(R7-1)") (class "Default")
      (node (ref "ALED") (pin "A") (pinfunction "A_A") (pintype "passive"))
      (node (ref "R7") (pin "P$1") (pinfunction "1_P$1") (pintype "passive"))
    )
    (net (code "53") (name "Net-(R12-2)") (class "Default")
      (node (ref "R12") (pin "P$2") (pinfunction "2_P$2") (pintype "passive"))
      (node (ref "XSTLED") (pin "A") (pinfunction "A_A") (pintype "passive"))
    )
    (net (code "54") (name "Net-(R13-2)") (class "Default")
      (node (ref "R13") (pin "P$2") (pinfunction "2_P$2") (pintype "passive"))
      (node (ref "YSTLED") (pin "A") (pinfunction "A_A") (pintype "passive"))
    )
    (net (code "55") (name "Net-(R14-2)") (class "Default")
      (node (ref "R14") (pin "P$2") (pinfunction "2_P$2") (pintype "passive"))
      (node (ref "ZSTLED") (pin "A") (pinfunction "A_A") (pintype "passive"))
    )
    (net (code "56") (name "Net-(STEPPERDRIVER-MOT-1A)") (class "Default")
      (node (ref "STEPPERDRIVER") (pin "1A") (pinfunction "MOT-1A_1A") (pintype "power_in"))
      (node (ref "XMOT") (pin "2") (pinfunction "KL_2") (pintype "passive"))
    )
    (net (code "57") (name "Net-(STEPPERDRIVER-MOT-1B)") (class "Default")
      (node (ref "STEPPERDRIVER") (pin "1B") (pinfunction "MOT-1B_1B") (pintype "power_in"))
      (node (ref "XMOT") (pin "1") (pinfunction "KL_1") (pintype "passive"))
    )
    (net (code "58") (name "Net-(STEPPERDRIVER-MOT-2A)") (class "Default")
      (node (ref "STEPPERDRIVER") (pin "2A") (pinfunction "MOT-2A_2A") (pintype "power_in"))
      (node (ref "XMOT") (pin "3") (pinfunction "KL_3") (pintype "passive"))
    )
    (net (code "59") (name "Net-(STEPPERDRIVER-MOT-2B)") (class "Default")
      (node (ref "STEPPERDRIVER") (pin "2B") (pinfunction "MOT-2B_2B") (pintype "power_in"))
      (node (ref "XMOT") (pin "4") (pinfunction "KL_4") (pintype "passive"))
    )
    (net (code "60") (name "Net-(STEPPERDRIVER-PadMS1)") (class "Default")
      (node (ref "STEPPERDRIVER") (pin "MS1") (pinfunction "MS1_MS1") (pintype "input"))
      (node (ref "X-AXIS") (pin "2") (pinfunction "2_2") (pintype "passive"))
    )
    (net (code "61") (name "Net-(STEPPERDRIVER-PadMS2)") (class "Default")
      (node (ref "STEPPERDRIVER") (pin "MS2") (pinfunction "MS2_MS2") (pintype "input"))
      (node (ref "X-AXIS") (pin "4") (pinfunction "4_4") (pintype "passive"))
    )
    (net (code "62") (name "Net-(STEPPERDRIVER-PadMS3)") (class "Default")
      (node (ref "STEPPERDRIVER") (pin "MS3") (pinfunction "MS3_MS3") (pintype "input"))
      (node (ref "X-AXIS") (pin "6") (pinfunction "6_6") (pintype "passive"))
    )
    (net (code "63") (name "Net-(STEPPERDRIVER-~{RESET})") (class "Default")
      (node (ref "STEPPERDRIVER") (pin "!RST") (pinfunction "~{RESET}_!RST") (pintype "input"))
      (node (ref "STEPPERDRIVER") (pin "!SLP") (pinfunction "~{SLEEP}_!SLP") (pintype "input"))
    )
    (net (code "64") (name "Net-(STEPPERDRIVER1-MOT-1A)") (class "Default")
      (node (ref "STEPPERDRIVER1") (pin "1A") (pinfunction "MOT-1A_1A") (pintype "power_in"))
      (node (ref "YMOT") (pin "2") (pinfunction "KL_2") (pintype "passive"))
    )
    (net (code "65") (name "Net-(STEPPERDRIVER1-MOT-1B)") (class "Default")
      (node (ref "STEPPERDRIVER1") (pin "1B") (pinfunction "MOT-1B_1B") (pintype "power_in"))
      (node (ref "YMOT") (pin "1") (pinfunction "KL_1") (pintype "passive"))
    )
    (net (code "66") (name "Net-(STEPPERDRIVER1-MOT-2A)") (class "Default")
      (node (ref "STEPPERDRIVER1") (pin "2A") (pinfunction "MOT-2A_2A") (pintype "power_in"))
      (node (ref "YMOT") (pin "3") (pinfunction "KL_3") (pintype "passive"))
    )
    (net (code "67") (name "Net-(STEPPERDRIVER1-MOT-2B)") (class "Default")
      (node (ref "STEPPERDRIVER1") (pin "2B") (pinfunction "MOT-2B_2B") (pintype "power_in"))
      (node (ref "YMOT") (pin "4") (pinfunction "KL_4") (pintype "passive"))
    )
    (net (code "68") (name "Net-(STEPPERDRIVER1-PadMS1)") (class "Default")
      (node (ref "STEPPERDRIVER1") (pin "MS1") (pinfunction "MS1_MS1") (pintype "input"))
      (node (ref "Y-AXIS") (pin "2") (pinfunction "2_2") (pintype "passive"))
    )
    (net (code "69") (name "Net-(STEPPERDRIVER1-PadMS2)") (class "Default")
      (node (ref "STEPPERDRIVER1") (pin "MS2") (pinfunction "MS2_MS2") (pintype "input"))
      (node (ref "Y-AXIS") (pin "4") (pinfunction "4_4") (pintype "passive"))
    )
    (net (code "70") (name "Net-(STEPPERDRIVER1-PadMS3)") (class "Default")
      (node (ref "STEPPERDRIVER1") (pin "MS3") (pinfunction "MS3_MS3") (pintype "input"))
      (node (ref "Y-AXIS") (pin "6") (pinfunction "6_6") (pintype "passive"))
    )
    (net (code "71") (name "Net-(STEPPERDRIVER1-~{RESET})") (class "Default")
      (node (ref "STEPPERDRIVER1") (pin "!RST") (pinfunction "~{RESET}_!RST") (pintype "input"))
      (node (ref "STEPPERDRIVER1") (pin "!SLP") (pinfunction "~{SLEEP}_!SLP") (pintype "input"))
    )
    (net (code "72") (name "Net-(STEPPERDRIVER2-MOT-1A)") (class "Default")
      (node (ref "STEPPERDRIVER2") (pin "1A") (pinfunction "MOT-1A_1A") (pintype "power_in"))
      (node (ref "ZMOT") (pin "2") (pinfunction "KL_2") (pintype "passive"))
    )
    (net (code "73") (name "Net-(STEPPERDRIVER2-MOT-1B)") (class "Default")
      (node (ref "STEPPERDRIVER2") (pin "1B") (pinfunction "MOT-1B_1B") (pintype "power_in"))
      (node (ref "ZMOT") (pin "1") (pinfunction "KL_1") (pintype "passive"))
    )
    (net (code "74") (name "Net-(STEPPERDRIVER2-MOT-2A)") (class "Default")
      (node (ref "STEPPERDRIVER2") (pin "2A") (pinfunction "MOT-2A_2A") (pintype "power_in"))
      (node (ref "ZMOT") (pin "3") (pinfunction "KL_3") (pintype "passive"))
    )
    (net (code "75") (name "Net-(STEPPERDRIVER2-MOT-2B)") (class "Default")
      (node (ref "STEPPERDRIVER2") (pin "2B") (pinfunction "MOT-2B_2B") (pintype "power_in"))
      (node (ref "ZMOT") (pin "4") (pinfunction "KL_4") (pintype "passive"))
    )
    (net (code "76") (name "Net-(STEPPERDRIVER2-PadMS1)") (class "Default")
      (node (ref "STEPPERDRIVER2") (pin "MS1") (pinfunction "MS1_MS1") (pintype "input"))
      (node (ref "Z-AXIS") (pin "2") (pinfunction "2_2") (pintype "passive"))
    )
    (net (code "77") (name "Net-(STEPPERDRIVER2-PadMS2)") (class "Default")
      (node (ref "STEPPERDRIVER2") (pin "MS2") (pinfunction "MS2_MS2") (pintype "input"))
      (node (ref "Z-AXIS") (pin "4") (pinfunction "4_4") (pintype "passive"))
    )
    (net (code "78") (name "Net-(STEPPERDRIVER2-PadMS3)") (class "Default")
      (node (ref "STEPPERDRIVER2") (pin "MS3") (pinfunction "MS3_MS3") (pintype "input"))
      (node (ref "Z-AXIS") (pin "6") (pinfunction "6_6") (pintype "passive"))
    )
    (net (code "79") (name "Net-(STEPPERDRIVER2-~{RESET})") (class "Default")
      (node (ref "STEPPERDRIVER2") (pin "!RST") (pinfunction "~{RESET}_!RST") (pintype "input"))
      (node (ref "STEPPERDRIVER2") (pin "!SLP") (pinfunction "~{SLEEP}_!SLP") (pintype "input"))
    )
    (net (code "80") (name "Net-(STEPPERDRIVER3-~{RESET})") (class "Default")
      (node (ref "STEPPERDRIVER3") (pin "!RST") (pinfunction "~{RESET}_!RST") (pintype "input"))
      (node (ref "STEPPERDRIVER3") (pin "!SLP") (pinfunction "~{SLEEP}_!SLP") (pintype "input"))
    )
    (net (code "81") (name "unconnected-(TTL-Pad6)") (class "Default")
      (node (ref "TTL") (pin "6") (pinfunction "6_6") (pintype "passive"))
    )
  )
)
